# GVSwire1.net
KiCad netlist of a schematic drawn in EAGLE
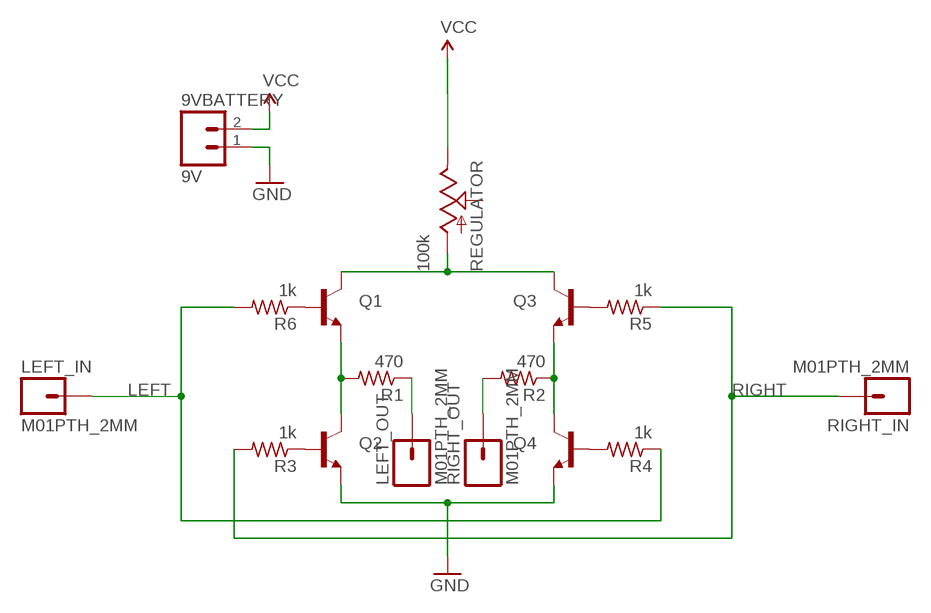
[diagram p0: schematic, sheet 1]

(export (version "E")
  (design (tool "Eeschema 10.0.6"))
  (components
    (comp (ref "9VBATTERY")
      (value "9V")
      (footprint "eagle-import:1X02_LONGPADS")
      (libsource (lib "eagle-import") (part "M02"))
    )
    (comp (ref "LEFT_IN")
      (value "M01PTH_2MM")
      (footprint "eagle-import:1X01_2MM")
      (libsource (lib "eagle-import") (part "M01PTH_2MM"))
    )
    (comp (ref "LEFT_OUT")
      (value "M01PTH_2MM")
      (footprint "eagle-import:1X01_2MM")
      (libsource (lib "eagle-import") (part "M01PTH_2MM"))
    )
    (comp (ref "Q1")
      (value "TRANSISTOR_NPNTO92")
      (footprint "eagle-import:TO-92")
      (libsource (lib "eagle-import") (part "TRANSISTOR_NPNTO92"))
    )
    (comp (ref "Q2")
      (value "TRANSISTOR_NPNTO92")
      (footprint "eagle-import:TO-92")
      (libsource (lib "eagle-import") (part "TRANSISTOR_NPNTO92"))
    )
    (comp (ref "Q3")
      (value "TRANSISTOR_NPNTO92")
      (footprint "eagle-import:TO-92")
      (libsource (lib "eagle-import") (part "TRANSISTOR_NPNTO92"))
    )
    (comp (ref "Q4")
      (value "TRANSISTOR_NPNTO92")
      (footprint "eagle-import:TO-92")
      (libsource (lib "eagle-import") (part "TRANSISTOR_NPNTO92"))
    )
    (comp (ref "R1")
      (value "470")
      (footprint "eagle-import:0805-THM-7")
      (libsource (lib "eagle-import") (part "R-US_FLIPFLOP7"))
    )
    (comp (ref "R2")
      (value "470")
      (footprint "eagle-import:0805-THM-7")
      (libsource (lib "eagle-import") (part "R-US_FLIPFLOP7"))
    )
    (comp (ref "R3")
      (value "1k")
      (footprint "eagle-import:0805-THM-7")
      (libsource (lib "eagle-import") (part "R-US_FLIPFLOP7"))
    )
    (comp (ref "R4")
      (value "1k")
      (footprint "eagle-import:0805-THM-7")
      (libsource (lib "eagle-import") (part "R-US_FLIPFLOP7"))
    )
    (comp (ref "R5")
      (value "1k")
      (footprint "eagle-import:0805-THM-7")
      (libsource (lib "eagle-import") (part "R-US_FLIPFLOP7"))
    )
    (comp (ref "R6")
      (value "1k")
      (footprint "eagle-import:0805-THM-7")
      (libsource (lib "eagle-import") (part "R-US_FLIPFLOP7"))
    )
    (comp (ref "REGULATOR")
      (value "100k")
      (footprint "eagle-import:ALPS_POT")
      (libsource (lib "eagle-import") (part "POT"))
    )
    (comp (ref "RIGHT_IN")
      (value "M01PTH_2MM")
      (footprint "eagle-import:1X01_2MM")
      (libsource (lib "eagle-import") (part "M01PTH_2MM"))
    )
    (comp (ref "RIGHT_OUT")
      (value "M01PTH_2MM")
      (footprint "eagle-import:1X01_2MM")
      (libsource (lib "eagle-import") (part "M01PTH_2MM"))
    )
  )
  (nets
    (net (code "1") (name "/LEFT") (class "Default")
      (node (ref "LEFT_IN") (pin "1") (pinfunction "1_1") (pintype "passive"))
      (node (ref "R4") (pin "1") (pinfunction "1_1") (pintype "passive"))
      (node (ref "R6") (pin "2") (pinfunction "2_2") (pintype "passive"))
    )
    (net (code "2") (name "/RIGHT") (class "Default")
      (node (ref "R3") (pin "2") (pinfunction "2_2") (pintype "passive"))
      (node (ref "R5") (pin "1") (pinfunction "1_1") (pintype "passive"))
      (node (ref "RIGHT_IN") (pin "1") (pinfunction "1_1") (pintype "passive"))
    )
    (net (code "3") (name "GND") (class "Default")
      (node (ref "9VBATTERY") (pin "1") (pinfunction "1_1") (pintype "passive"))
      (node (ref "Q2") (pin "1") (pinfunction "E_1") (pintype "passive"))
      (node (ref "Q4") (pin "1") (pinfunction "E_1") (pintype "passive"))
    )
    (net (code "4") (name "Net-(LEFT_OUT-Pad1)") (class "Default")
      (node (ref "LEFT_OUT") (pin "1") (pinfunction "1_1") (pintype "passive"))
      (node (ref "R1") (pin "1") (pinfunction "1_1") (pintype "passive"))
    )
    (net (code "5") (name "Net-(Q1-B)") (class "Default")
      (node (ref "Q1") (pin "2") (pinfunction "B_2") (pintype "passive"))
      (node (ref "R6") (pin "1") (pinfunction "1_1") (pintype "passive"))
    )
    (net (code "6") (name "Net-(Q1-C)") (class "Default")
      (node (ref "Q1") (pin "3") (pinfunction "C_3") (pintype "passive"))
      (node (ref "Q3") (pin "3") (pinfunction "C_3") (pintype "passive"))
      (node (ref "REGULATOR") (pin "P$3") (pinfunction "A_P$3") (pintype "passive"))
    )
    (net (code "7") (name "Net-(Q1-E)") (class "Default")
      (node (ref "Q1") (pin "1") (pinfunction "E_1") (pintype "passive"))
      (node (ref "Q2") (pin "3") (pinfunction "C_3") (pintype "passive"))
      (node (ref "R1") (pin "2") (pinfunction "2_2") (pintype "passive"))
    )
    (net (code "8") (name "Net-(Q2-B)") (class "Default")
      (node (ref "Q2") (pin "2") (pinfunction "B_2") (pintype "passive"))
      (node (ref "R3") (pin "1") (pinfunction "1_1") (pintype "passive"))
    )
    (net (code "9") (name "Net-(Q3-B)") (class "Default")
      (node (ref "Q3") (pin "2") (pinfunction "B_2") (pintype "passive"))
      (node (ref "R5") (pin "2") (pinfunction "2_2") (pintype "passive"))
    )
    (net (code "10") (name "Net-(Q3-E)") (class "Default")
      (node (ref "Q3") (pin "1") (pinfunction "E_1") (pintype "passive"))
      (node (ref "Q4") (pin "3") (pinfunction "C_3") (pintype "passive"))
      (node (ref "R2") (pin "1") (pinfunction "1_1") (pintype "passive"))
    )
    (net (code "11") (name "Net-(Q4-B)") (class "Default")
      (node (ref "Q4") (pin "2") (pinfunction "B_2") (pintype "passive"))
      (node (ref "R4") (pin "2") (pinfunction "2_2") (pintype "passive"))
    )
    (net (code "12") (name "Net-(R2-Pad2)") (class "Default")
      (node (ref "R2") (pin "2") (pinfunction "2_2") (pintype "passive"))
      (node (ref "RIGHT_OUT") (pin "1") (pinfunction "1_1") (pintype "passive"))
    )
    (net (code "13") (name "VCC") (class "Default")
      (node (ref "9VBATTERY") (pin "2") (pinfunction "2_2") (pintype "passive"))
      (node (ref "REGULATOR") (pin "P$1") (pinfunction "E_P$1") (pintype "passive"))
    )
    (net (code "14") (name "unconnected-(REGULATOR-S-PadP$2)") (class "Default")
      (node (ref "REGULATOR") (pin "P$2") (pinfunction "S_P$2") (pintype "passive"))
    )
  )
)
